# sensors.net
KiCad netlist of a schematic drawn in EAGLE
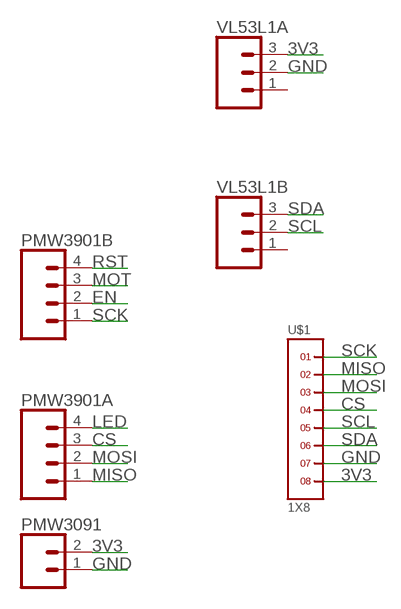
[diagram p0: schematic, sheet 1]

(export (version "E")
  (design (tool "Eeschema 10.0.6"))
  (components
    (comp (ref "PMW3091")
      (value "CONN_021X02_NO_SILK")
      (footprint "eagle-import:1X02_NO_SILK")
      (libsource (lib "eagle-import") (part "CONN_021X02_NO_SILK"))
    )
    (comp (ref "PMW3901A")
      (value "CONN_041X04_NO_SILK")
      (footprint "eagle-import:1X04_NO_SILK")
      (libsource (lib "eagle-import") (part "CONN_041X04_NO_SILK"))
    )
    (comp (ref "PMW3901B")
      (value "CONN_041X04_NO_SILK")
      (footprint "eagle-import:1X04_NO_SILK")
      (libsource (lib "eagle-import") (part "CONN_041X04_NO_SILK"))
    )
    (comp (ref "U$1")
      (value "1X8")
      (footprint "eagle-import:1X8")
      (libsource (lib "eagle-import") (part "1X8"))
    )
    (comp (ref "VL53L1A")
      (value "CONN_031X03_NO_SILK")
      (footprint "eagle-import:1X03_NO_SILK")
      (libsource (lib "eagle-import") (part "CONN_031X03_NO_SILK"))
    )
    (comp (ref "VL53L1B")
      (value "CONN_031X03_NO_SILK")
      (footprint "eagle-import:1X03_NO_SILK")
      (libsource (lib "eagle-import") (part "CONN_031X03_NO_SILK"))
    )
  )
  (nets
    (net (code "1") (name "/3V3") (class "Default")
      (node (ref "PMW3091") (pin "2") (pinfunction "2_2") (pintype "passive"))
      (node (ref "U$1") (pin "8") (pinfunction "8_8") (pintype "bidirectional"))
      (node (ref "VL53L1A") (pin "3") (pinfunction "3_3") (pintype "passive"))
    )
    (net (code "2") (name "/CS") (class "Default")
      (node (ref "PMW3901A") (pin "3") (pinfunction "3_3") (pintype "passive"))
      (node (ref "U$1") (pin "4") (pinfunction "4_4") (pintype "bidirectional"))
    )
    (net (code "3") (name "/EN") (class "Default")
      (node (ref "PMW3901B") (pin "2") (pinfunction "2_2") (pintype "passive"))
    )
    (net (code "4") (name "/GND") (class "Default")
      (node (ref "PMW3091") (pin "1") (pinfunction "1_1") (pintype "passive"))
      (node (ref "U$1") (pin "7") (pinfunction "7_7") (pintype "bidirectional"))
      (node (ref "VL53L1A") (pin "2") (pinfunction "2_2") (pintype "passive"))
    )
    (net (code "5") (name "/LED") (class "Default")
      (node (ref "PMW3901A") (pin "4") (pinfunction "4_4") (pintype "passive"))
    )
    (net (code "6") (name "/MISO") (class "Default")
      (node (ref "PMW3901A") (pin "1") (pinfunction "1_1") (pintype "passive"))
      (node (ref "U$1") (pin "2") (pinfunction "2_2") (pintype "bidirectional"))
    )
    (net (code "7") (name "/MOSI") (class "Default")
      (node (ref "PMW3901A") (pin "2") (pinfunction "2_2") (pintype "passive"))
      (node (ref "U$1") (pin "3") (pinfunction "3_3") (pintype "bidirectional"))
    )
    (net (code "8") (name "/MOT") (class "Default")
      (node (ref "PMW3901B") (pin "3") (pinfunction "3_3") (pintype "passive"))
    )
    (net (code "9") (name "/RST") (class "Default")
      (node (ref "PMW3901B") (pin "4") (pinfunction "4_4") (pintype "passive"))
    )
    (net (code "10") (name "/SCK") (class "Default")
      (node (ref "PMW3901B") (pin "1") (pinfunction "1_1") (pintype "passive"))
      (node (ref "U$1") (pin "1") (pinfunction "1_1") (pintype "bidirectional"))
    )
    (net (code "11") (name "/SCL") (class "Default")
      (node (ref "U$1") (pin "5") (pinfunction "5_5") (pintype "bidirectional"))
      (node (ref "VL53L1B") (pin "2") (pinfunction "2_2") (pintype "passive"))
    )
    (net (code "12") (name "/SDA") (class "Default")
      (node (ref "U$1") (pin "6") (pinfunction "6_6") (pintype "bidirectional"))
      (node (ref "VL53L1B") (pin "3") (pinfunction "3_3") (pintype "passive"))
    )
    (net (code "13") (name "unconnected-(VL53L1A-Pad1)") (class "Default")
      (node (ref "VL53L1A") (pin "1") (pinfunction "1_1") (pintype "passive"))
    )
    (net (code "14") (name "unconnected-(VL53L1B-Pad1)") (class "Default")
      (node (ref "VL53L1B") (pin "1") (pinfunction "1_1") (pintype "passive"))
    )
  )
)
